# 09_NET_Interface.net
KiCad netlist of a schematic drawn in Altium Designer
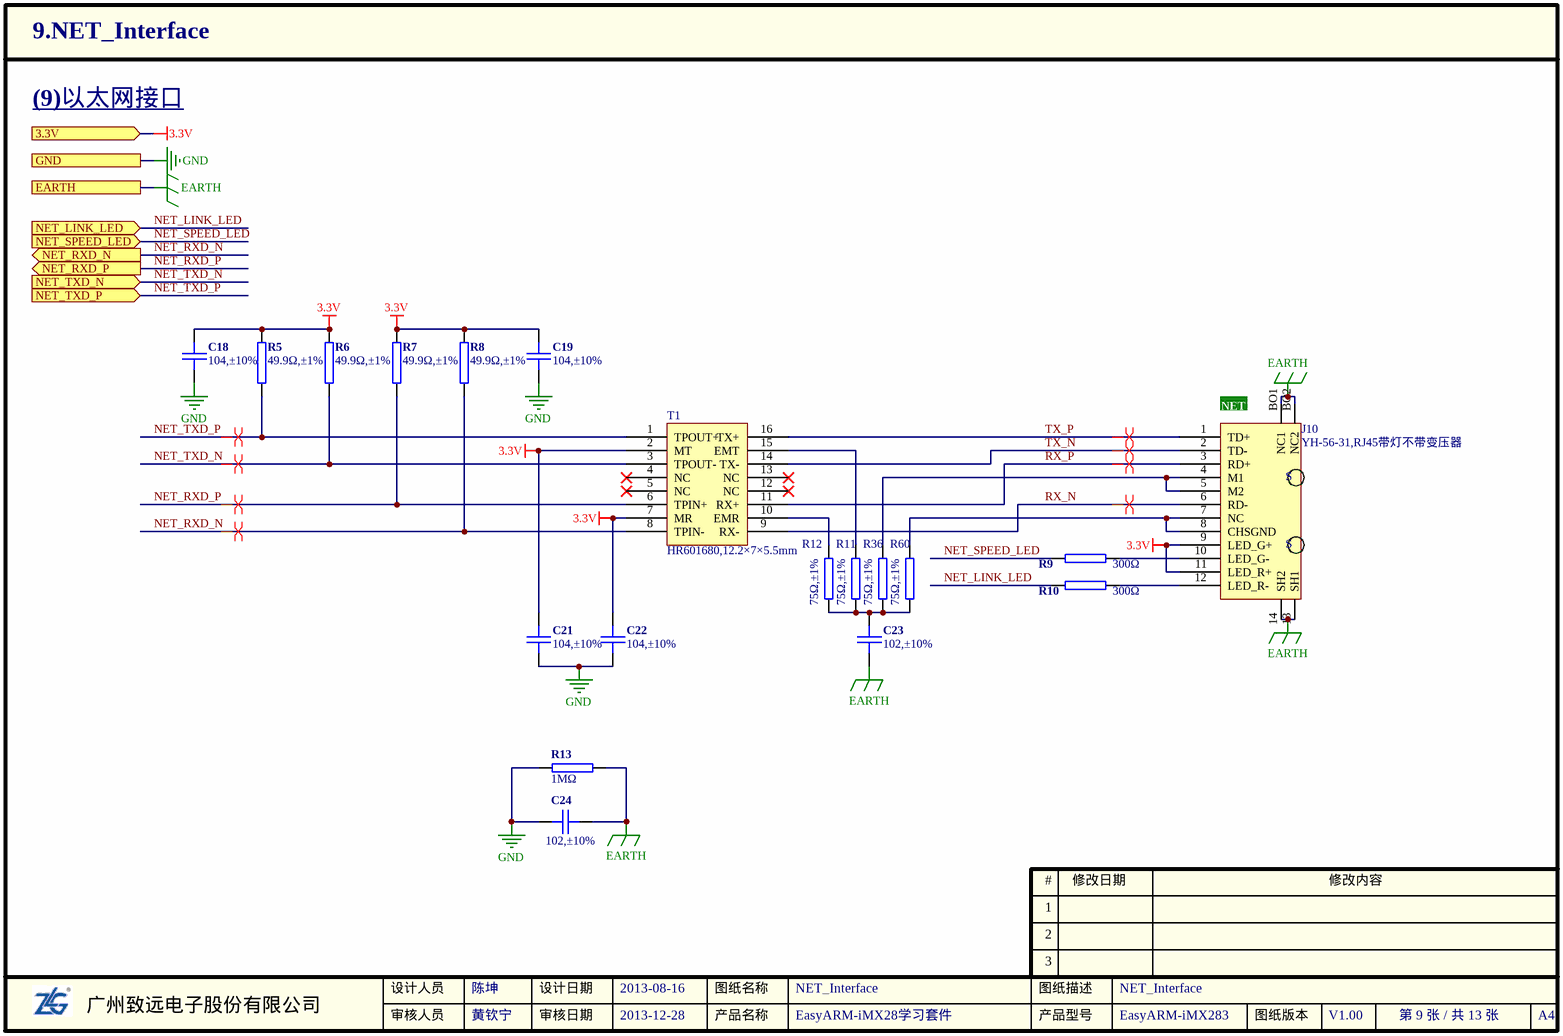
[diagram p0: 09. NET_Interface.SchDoc]

(export (version "E")
  (design (tool "Eeschema 10.0.6"))
  (components
    (comp (ref "C18")
      (value "104,±10%")
      (footprint "0603C")
      (description "104,±10%,50V,X7R,0603,*,RoHS")
      (libsource (lib "ErpMaterialData") (part "CAP1"))
    )
    (comp (ref "C19")
      (value "104,±10%")
      (footprint "0603C")
      (description "104,±10%,50V,X7R,0603,*,RoHS")
      (libsource (lib "ErpMaterialData") (part "CAP1"))
    )
    (comp (ref "C21")
      (value "104,±10%")
      (footprint "0603C")
      (description "104,±10%,50V,X7R,0603,*,RoHS")
      (libsource (lib "ErpMaterialData") (part "CAP1"))
    )
    (comp (ref "C22")
      (value "104,±10%")
      (footprint "0603C")
      (description "104,±10%,50V,X7R,0603,*,RoHS")
      (libsource (lib "ErpMaterialData") (part "CAP1"))
    )
    (comp (ref "C23")
      (value "102,±10%")
      (footprint "1206C")
      (description "102,±10%,2KV,X7R,1206,*,RoHS")
      (libsource (lib "ErpMaterialData") (part "CAP1"))
    )
    (comp (ref "C24")
      (value "102,±10%")
      (footprint "1206C")
      (description "Capacitor")
      (libsource (lib "ErpMaterialData") (part "CAP1"))
    )
    (comp (ref "J10")
      (value "YH-56-31,RJ45带灯不带变压器")
      (footprint "RJ45/LED")
      (fields (field (name "Comment") "HR911105C"))
      (libsource (lib "ErpMaterialData") (part "NET-HR911105"))
    )
    (comp (ref "R5")
      (value "49.9Ω,±1%")
      (footprint "0603R")
      (description "49.9Ω,±1%,0603,*,RoHS")
      (libsource (lib "ErpMaterialData") (part "RES2"))
    )
    (comp (ref "R6")
      (value "49.9Ω,±1%")
      (footprint "0603R")
      (description "49.9Ω,±1%,0603,*,RoHS")
      (libsource (lib "ErpMaterialData") (part "RES2"))
    )
    (comp (ref "R7")
      (value "49.9Ω,±1%")
      (footprint "0603R")
      (description "49.9Ω,±1%,0603,*,RoHS")
      (libsource (lib "ErpMaterialData") (part "RES2"))
    )
    (comp (ref "R8")
      (value "49.9Ω,±1%")
      (footprint "0603R")
      (description "49.9Ω,±1%,0603,*,RoHS")
      (libsource (lib "ErpMaterialData") (part "RES2"))
    )
    (comp (ref "R9")
      (value "300Ω")
      (footprint "0603R")
      (description "300Ω,0603,*,RoHS")
      (libsource (lib "ErpMaterialData") (part "RES2"))
    )
    (comp (ref "R10")
      (value "300Ω")
      (footprint "0603R")
      (description "300Ω,0603,*,RoHS")
      (libsource (lib "ErpMaterialData") (part "RES2"))
    )
    (comp (ref "R11")
      (value "75Ω,±1%")
      (footprint "0603R")
      (description "75Ω,±1%,0603,*,RoHS")
      (libsource (lib "ErpMaterialData") (part "RES2"))
    )
    (comp (ref "R12")
      (value "75Ω,±1%")
      (footprint "0603R")
      (description "75Ω,±1%,0603,*,RoHS")
      (libsource (lib "ErpMaterialData") (part "RES2"))
    )
    (comp (ref "R13") (value "1MΩ") (footprint "1206R") (libsource (lib "ErpMaterialData") (part "RES2")))
    (comp (ref "R36")
      (value "75Ω,±1%")
      (footprint "0603R")
      (description "75Ω,±1%,0603,*,RoHS")
      (libsource (lib "ErpMaterialData") (part "RES2"))
    )
    (comp (ref "R60")
      (value "75Ω,±1%")
      (footprint "0603R")
      (description "75Ω,±1%,0603,*,RoHS")
      (libsource (lib "ErpMaterialData") (part "RES2"))
    )
    (comp (ref "T1")
      (value "HR601680,12.2×7×5.5mm")
      (footprint "TRAN16-12R2X7X5R5-SM")
      (description "HR601680,12.2×7×5.5mm,SOP-16,RoHS")
      (fields (field (name "Comment") "HR601680"))
      (libsource (lib "ErpMaterialData") (part "HR601680"))
    )
  )
  (nets
    (net (code "1") (name "/NET_LINK_LED") (class "Default")
      (node (ref "R10") (pin "1") (pinfunction "1_1") (pintype "passive"))
    )
    (net (code "2") (name "/NET_RXD_N") (class "Default")
      (node (ref "R8") (pin "2") (pinfunction "2_2") (pintype "passive"))
      (node (ref "T1") (pin "8") (pinfunction "TPIN-_8") (pintype "passive"))
    )
    (net (code "3") (name "/NET_RXD_P") (class "Default")
      (node (ref "R7") (pin "1") (pinfunction "1_1") (pintype "passive"))
      (node (ref "T1") (pin "6") (pinfunction "TPIN+_6") (pintype "passive"))
    )
    (net (code "4") (name "/NET_SPEED_LED") (class "Default")
      (node (ref "R9") (pin "1") (pinfunction "1_1") (pintype "passive"))
    )
    (net (code "5") (name "/NET_TXD_N") (class "Default")
      (node (ref "R6") (pin "2") (pinfunction "2_2") (pintype "passive"))
      (node (ref "T1") (pin "3") (pinfunction "TPOUT-_3") (pintype "passive"))
    )
    (net (code "6") (name "/NET_TXD_P") (class "Default")
      (node (ref "R5") (pin "2") (pinfunction "2_2") (pintype "passive"))
      (node (ref "T1") (pin "1") (pinfunction "TPOUT+_1") (pintype "passive"))
    )
    (net (code "7") (name "/RX_N") (class "Default")
      (node (ref "J10") (pin "6") (pinfunction "RD-_6") (pintype "passive"))
      (node (ref "T1") (pin "9") (pinfunction "RX-_9") (pintype "passive"))
    )
    (net (code "8") (name "/RX_P") (class "Default")
      (node (ref "J10") (pin "3") (pinfunction "RD+_3") (pintype "passive"))
      (node (ref "T1") (pin "11") (pinfunction "RX+_11") (pintype "passive"))
    )
    (net (code "9") (name "/TX_N") (class "Default")
      (node (ref "J10") (pin "2") (pinfunction "TD-_2") (pintype "passive"))
      (node (ref "T1") (pin "14") (pinfunction "TX-_14") (pintype "passive"))
    )
    (net (code "10") (name "/TX_P") (class "Default")
      (node (ref "J10") (pin "1") (pinfunction "TD+_1") (pintype "passive"))
      (node (ref "T1") (pin "16") (pinfunction "TX+_16") (pintype "passive"))
    )
    (net (code "11") (name "3.3V") (class "Default")
      (node (ref "C18") (pin "1") (pinfunction "1_1") (pintype "passive"))
      (node (ref "C19") (pin "1") (pinfunction "1_1") (pintype "passive"))
      (node (ref "C21") (pin "1") (pinfunction "1_1") (pintype "passive"))
      (node (ref "C22") (pin "1") (pinfunction "1_1") (pintype "passive"))
      (node (ref "J10") (pin "11") (pinfunction "LED_R+_11") (pintype "passive"))
      (node (ref "J10") (pin "9") (pinfunction "LED_G+_9") (pintype "passive"))
      (node (ref "R5") (pin "1") (pinfunction "1_1") (pintype "passive"))
      (node (ref "R6") (pin "1") (pinfunction "1_1") (pintype "passive"))
      (node (ref "R7") (pin "2") (pinfunction "2_2") (pintype "passive"))
      (node (ref "R8") (pin "1") (pinfunction "1_1") (pintype "passive"))
      (node (ref "T1") (pin "2") (pinfunction "MT_2") (pintype "passive"))
      (node (ref "T1") (pin "7") (pinfunction "MR_7") (pintype "passive"))
    )
    (net (code "12") (name "EARTH") (class "Default")
      (node (ref "C23") (pin "2") (pinfunction "2_2") (pintype "passive"))
      (node (ref "C24") (pin "2") (pinfunction "2_2") (pintype "passive"))
      (node (ref "J10") (pin "13") (pinfunction "SH1_13") (pintype "passive"))
      (node (ref "J10") (pin "14") (pinfunction "SH2_14") (pintype "passive"))
      (node (ref "J10") (pin "BO1") (pinfunction "NC1_BO1") (pintype "passive"))
      (node (ref "J10") (pin "BO2") (pinfunction "NC2_BO2") (pintype "passive"))
      (node (ref "R13") (pin "2") (pinfunction "2_2") (pintype "passive"))
    )
    (net (code "13") (name "GND") (class "Default")
      (node (ref "C18") (pin "2") (pinfunction "2_2") (pintype "passive"))
      (node (ref "C19") (pin "2") (pinfunction "2_2") (pintype "passive"))
      (node (ref "C21") (pin "2") (pinfunction "2_2") (pintype "passive"))
      (node (ref "C22") (pin "2") (pinfunction "2_2") (pintype "passive"))
      (node (ref "C24") (pin "1") (pinfunction "1_1") (pintype "passive"))
      (node (ref "R13") (pin "1") (pinfunction "1_1") (pintype "passive"))
    )
    (net (code "14") (name "Net-(C23-Pad1)") (class "Default")
      (node (ref "C23") (pin "1") (pinfunction "1_1") (pintype "passive"))
      (node (ref "R11") (pin "1") (pinfunction "1_1") (pintype "passive"))
      (node (ref "R12") (pin "1") (pinfunction "1_1") (pintype "passive"))
      (node (ref "R36") (pin "1") (pinfunction "1_1") (pintype "passive"))
      (node (ref "R60") (pin "1") (pinfunction "1_1") (pintype "passive"))
    )
    (net (code "15") (name "Net-(J10-CHSGND)") (class "Default")
      (node (ref "J10") (pin "7") (pinfunction "NC_7") (pintype "passive"))
      (node (ref "J10") (pin "8") (pinfunction "CHSGND_8") (pintype "passive"))
      (node (ref "R60") (pin "2") (pinfunction "2_2") (pintype "passive"))
    )
    (net (code "16") (name "Net-(J10-LED_G-)") (class "Default")
      (node (ref "J10") (pin "10") (pinfunction "LED_G-_10") (pintype "passive"))
      (node (ref "R9") (pin "2") (pinfunction "2_2") (pintype "passive"))
    )
    (net (code "17") (name "Net-(J10-LED_R-)") (class "Default")
      (node (ref "J10") (pin "12") (pinfunction "LED_R-_12") (pintype "passive"))
      (node (ref "R10") (pin "2") (pinfunction "2_2") (pintype "passive"))
    )
    (net (code "18") (name "Net-(J10-M1)") (class "Default")
      (node (ref "J10") (pin "4") (pinfunction "M1_4") (pintype "passive"))
      (node (ref "J10") (pin "5") (pinfunction "M2_5") (pintype "passive"))
      (node (ref "R36") (pin "2") (pinfunction "2_2") (pintype "passive"))
    )
    (net (code "19") (name "Net-(T1-EMR)") (class "Default")
      (node (ref "R12") (pin "2") (pinfunction "2_2") (pintype "passive"))
      (node (ref "T1") (pin "10") (pinfunction "EMR_10") (pintype "passive"))
    )
    (net (code "20") (name "Net-(T1-EMT)") (class "Default")
      (node (ref "R11") (pin "2") (pinfunction "2_2") (pintype "passive"))
      (node (ref "T1") (pin "15") (pinfunction "EMT_15") (pintype "passive"))
    )
    (net (code "21") (name "unconnected-(T1-NC-Pad4)") (class "Default")
      (node (ref "T1") (pin "4") (pinfunction "NC_4") (pintype "passive+no_connect"))
    )
    (net (code "22") (name "unconnected-(T1-NC-Pad5)") (class "Default")
      (node (ref "T1") (pin "5") (pinfunction "NC_5") (pintype "passive+no_connect"))
    )
    (net (code "23") (name "unconnected-(T1-NC-Pad12)") (class "Default")
      (node (ref "T1") (pin "12") (pinfunction "NC_12") (pintype "passive+no_connect"))
    )
    (net (code "24") (name "unconnected-(T1-NC-Pad13)") (class "Default")
      (node (ref "T1") (pin "13") (pinfunction "NC_13") (pintype "passive+no_connect"))
    )
  )
)
